# Q1_EAGLE_BRD.net
KiCad netlist of a schematic drawn in EAGLE
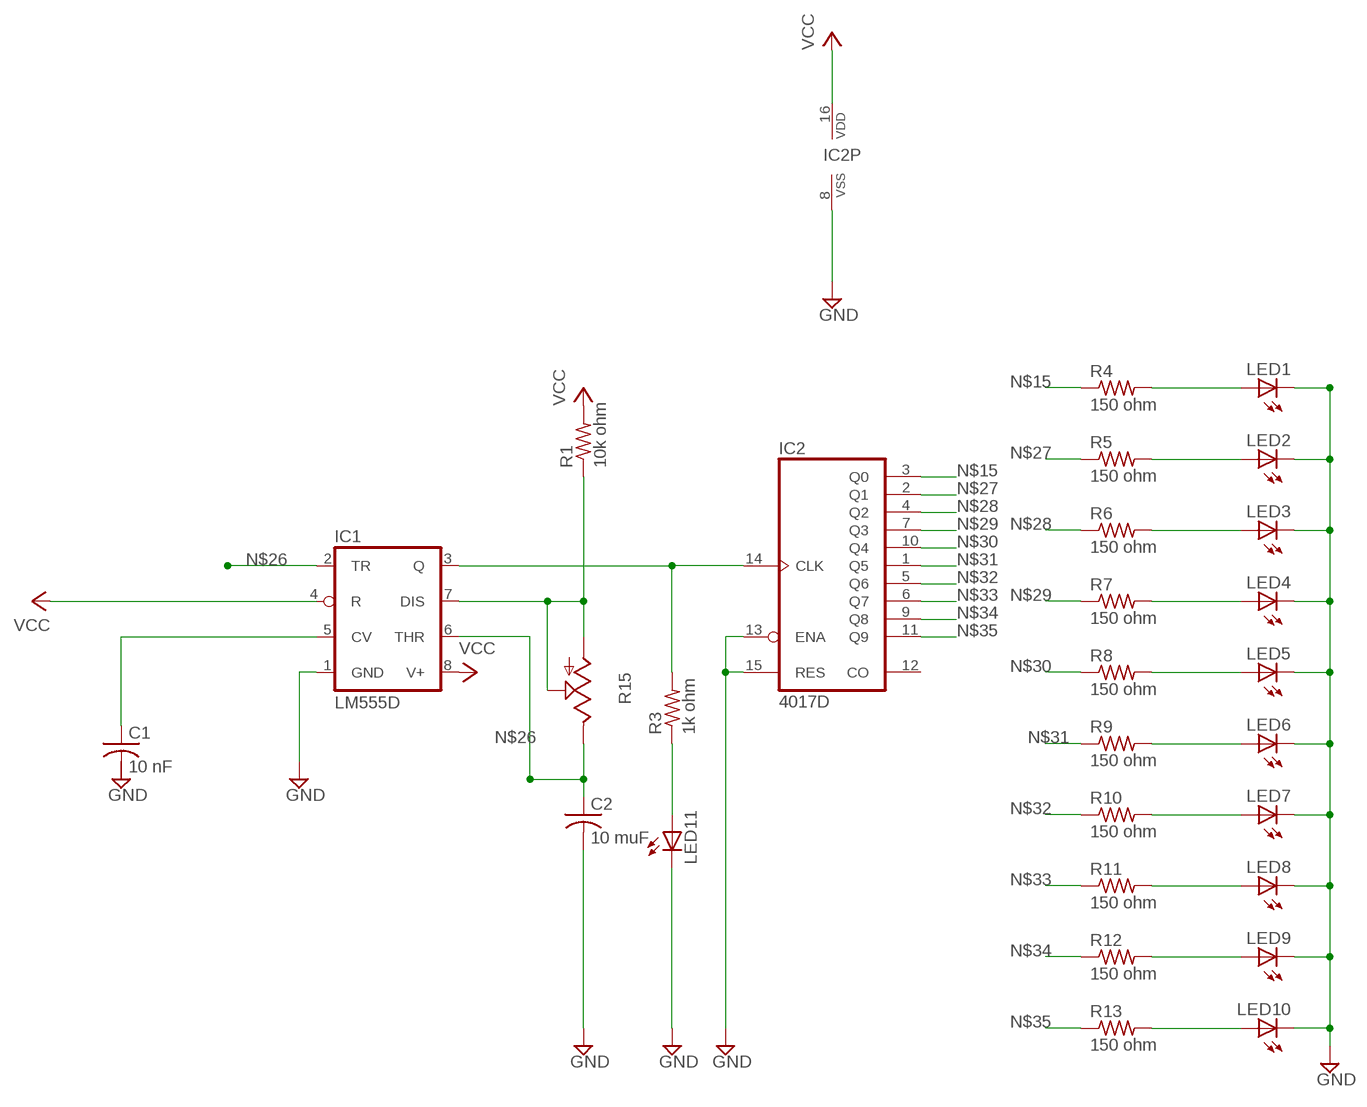
[diagram p0: schematic, sheet 1]

(export (version "E")
  (design (tool "Eeschema 10.0.6"))
  (components
    (comp (ref "C1")
      (value "10 nF")
      (footprint "eagle-import:C0805")
      (libsource (lib "eagle-import") (part "C-USC0805"))
    )
    (comp (ref "C2")
      (value "10 muF")
      (footprint "eagle-import:C0805")
      (libsource (lib "eagle-import") (part "C-USC0805"))
    )
    (comp (ref "IC1")
      (value "LM555D")
      (footprint "eagle-import:SO08")
      (libsource (lib "eagle-import") (part "555DLM"))
    )
    (comp (ref "IC2")
      (value "4017D")
      (footprint "eagle-import:SO16")
      (libsource (lib "eagle-import") (part "4017D"))
    )
    (comp (ref "LED1")
      (value "LED5MM")
      (footprint "eagle-import:LED5MM")
      (libsource (lib "eagle-import") (part "LED5MM"))
    )
    (comp (ref "LED2")
      (value "LED5MM")
      (footprint "eagle-import:LED5MM")
      (libsource (lib "eagle-import") (part "LED5MM"))
    )
    (comp (ref "LED3")
      (value "LED5MM")
      (footprint "eagle-import:LED5MM")
      (libsource (lib "eagle-import") (part "LED5MM"))
    )
    (comp (ref "LED4")
      (value "LED5MM")
      (footprint "eagle-import:LED5MM")
      (libsource (lib "eagle-import") (part "LED5MM"))
    )
    (comp (ref "LED5")
      (value "LED5MM")
      (footprint "eagle-import:LED5MM")
      (libsource (lib "eagle-import") (part "LED5MM"))
    )
    (comp (ref "LED6")
      (value "LED5MM")
      (footprint "eagle-import:LED5MM")
      (libsource (lib "eagle-import") (part "LED5MM"))
    )
    (comp (ref "LED7")
      (value "LED5MM")
      (footprint "eagle-import:LED5MM")
      (libsource (lib "eagle-import") (part "LED5MM"))
    )
    (comp (ref "LED8")
      (value "LED5MM")
      (footprint "eagle-import:LED5MM")
      (libsource (lib "eagle-import") (part "LED5MM"))
    )
    (comp (ref "LED9")
      (value "LED5MM")
      (footprint "eagle-import:LED5MM")
      (libsource (lib "eagle-import") (part "LED5MM"))
    )
    (comp (ref "LED10")
      (value "LED5MM")
      (footprint "eagle-import:LED5MM")
      (libsource (lib "eagle-import") (part "LED5MM"))
    )
    (comp (ref "LED11")
      (value "LED5MM")
      (footprint "eagle-import:LED5MM")
      (libsource (lib "eagle-import") (part "LED5MM"))
    )
    (comp (ref "R1")
      (value "10k ohm")
      (footprint "eagle-import:M1206")
      (libsource (lib "eagle-import") (part "R-US_M1206"))
    )
    (comp (ref "R3")
      (value "1k ohm")
      (footprint "eagle-import:M1206")
      (libsource (lib "eagle-import") (part "R-US_M1206"))
    )
    (comp (ref "R4")
      (value "150 ohm")
      (footprint "eagle-import:M1206")
      (libsource (lib "eagle-import") (part "R-US_M1206"))
    )
    (comp (ref "R5")
      (value "150 ohm")
      (footprint "eagle-import:M1206")
      (libsource (lib "eagle-import") (part "R-US_M1206"))
    )
    (comp (ref "R6")
      (value "150 ohm")
      (footprint "eagle-import:M1206")
      (libsource (lib "eagle-import") (part "R-US_M1206"))
    )
    (comp (ref "R7")
      (value "150 ohm")
      (footprint "eagle-import:M1206")
      (libsource (lib "eagle-import") (part "R-US_M1206"))
    )
    (comp (ref "R8")
      (value "150 ohm")
      (footprint "eagle-import:M1206")
      (libsource (lib "eagle-import") (part "R-US_M1206"))
    )
    (comp (ref "R9")
      (value "150 ohm")
      (footprint "eagle-import:M1206")
      (libsource (lib "eagle-import") (part "R-US_M1206"))
    )
    (comp (ref "R10")
      (value "150 ohm")
      (footprint "eagle-import:M1206")
      (libsource (lib "eagle-import") (part "R-US_M1206"))
    )
    (comp (ref "R11")
      (value "150 ohm")
      (footprint "eagle-import:M1206")
      (libsource (lib "eagle-import") (part "R-US_M1206"))
    )
    (comp (ref "R12")
      (value "150 ohm")
      (footprint "eagle-import:M1206")
      (libsource (lib "eagle-import") (part "R-US_M1206"))
    )
    (comp (ref "R13")
      (value "150 ohm")
      (footprint "eagle-import:M1206")
      (libsource (lib "eagle-import") (part "R-US_M1206"))
    )
    (comp (ref "R15")
      (value "TRIM_US-S63X")
      (footprint "eagle-import:S63X")
      (libsource (lib "eagle-import") (part "TRIM_US-S63X"))
    )
  )
  (nets
    (net (code "1") (name "/N$15") (class "Default")
      (node (ref "IC2") (pin "3") (pinfunction "Q0_3") (pintype "output"))
      (node (ref "R4") (pin "1") (pinfunction "1_1") (pintype "passive"))
    )
    (net (code "2") (name "/N$26") (class "Default")
      (node (ref "C2") (pin "1") (pinfunction "1_1") (pintype "passive"))
      (node (ref "IC1") (pin "2") (pinfunction "TR_2") (pintype "input"))
      (node (ref "IC1") (pin "6") (pinfunction "THR_6") (pintype "input"))
      (node (ref "R15") (pin "E") (pinfunction "E_E") (pintype "passive"))
    )
    (net (code "3") (name "/N$27") (class "Default")
      (node (ref "IC2") (pin "2") (pinfunction "Q1_2") (pintype "output"))
      (node (ref "R5") (pin "1") (pinfunction "1_1") (pintype "passive"))
    )
    (net (code "4") (name "/N$28") (class "Default")
      (node (ref "IC2") (pin "4") (pinfunction "Q2_4") (pintype "output"))
      (node (ref "R6") (pin "1") (pinfunction "1_1") (pintype "passive"))
    )
    (net (code "5") (name "/N$29") (class "Default")
      (node (ref "IC2") (pin "7") (pinfunction "Q3_7") (pintype "output"))
      (node (ref "R7") (pin "1") (pinfunction "1_1") (pintype "passive"))
    )
    (net (code "6") (name "/N$30") (class "Default")
      (node (ref "IC2") (pin "10") (pinfunction "Q4_10") (pintype "output"))
      (node (ref "R8") (pin "1") (pinfunction "1_1") (pintype "passive"))
    )
    (net (code "7") (name "/N$31") (class "Default")
      (node (ref "IC2") (pin "1") (pinfunction "Q5_1") (pintype "output"))
      (node (ref "R9") (pin "1") (pinfunction "1_1") (pintype "passive"))
    )
    (net (code "8") (name "/N$32") (class "Default")
      (node (ref "IC2") (pin "5") (pinfunction "Q6_5") (pintype "output"))
      (node (ref "R10") (pin "1") (pinfunction "1_1") (pintype "passive"))
    )
    (net (code "9") (name "/N$33") (class "Default")
      (node (ref "IC2") (pin "6") (pinfunction "Q7_6") (pintype "output"))
      (node (ref "R11") (pin "1") (pinfunction "1_1") (pintype "passive"))
    )
    (net (code "10") (name "/N$34") (class "Default")
      (node (ref "IC2") (pin "9") (pinfunction "Q8_9") (pintype "output"))
      (node (ref "R12") (pin "1") (pinfunction "1_1") (pintype "passive"))
    )
    (net (code "11") (name "/N$35") (class "Default")
      (node (ref "IC2") (pin "11") (pinfunction "Q9_11") (pintype "output"))
      (node (ref "R13") (pin "1") (pinfunction "1_1") (pintype "passive"))
    )
    (net (code "12") (name "GND") (class "Default")
      (node (ref "C2") (pin "2") (pinfunction "2_2") (pintype "passive"))
      (node (ref "IC1") (pin "1") (pinfunction "GND_1") (pintype "power_in"))
      (node (ref "IC2") (pin "13") (pinfunction "ENA_13") (pintype "input"))
      (node (ref "IC2") (pin "15") (pinfunction "RES_15") (pintype "input"))
      (node (ref "IC2") (pin "8") (pinfunction "VSS_8") (pintype "power_in"))
      (node (ref "LED1") (pin "K") (pinfunction "C_K") (pintype "passive"))
      (node (ref "LED10") (pin "K") (pinfunction "C_K") (pintype "passive"))
      (node (ref "LED11") (pin "K") (pinfunction "C_K") (pintype "passive"))
      (node (ref "LED2") (pin "K") (pinfunction "C_K") (pintype "passive"))
      (node (ref "LED3") (pin "K") (pinfunction "C_K") (pintype "passive"))
      (node (ref "LED4") (pin "K") (pinfunction "C_K") (pintype "passive"))
      (node (ref "LED5") (pin "K") (pinfunction "C_K") (pintype "passive"))
      (node (ref "LED6") (pin "K") (pinfunction "C_K") (pintype "passive"))
      (node (ref "LED7") (pin "K") (pinfunction "C_K") (pintype "passive"))
      (node (ref "LED8") (pin "K") (pinfunction "C_K") (pintype "passive"))
      (node (ref "LED9") (pin "K") (pinfunction "C_K") (pintype "passive"))
    )
    (net (code "13") (name "Net-(IC1-CV)") (class "Default")
      (node (ref "C1") (pin "1") (pinfunction "1_1") (pintype "passive"))
      (node (ref "IC1") (pin "5") (pinfunction "CV_5") (pintype "input"))
    )
    (net (code "14") (name "Net-(IC1-DIS)") (class "Default")
      (node (ref "IC1") (pin "7") (pinfunction "DIS_7") (pintype "input"))
      (node (ref "R1") (pin "1") (pinfunction "1_1") (pintype "passive"))
      (node (ref "R15") (pin "A") (pinfunction "A_A") (pintype "passive"))
      (node (ref "R15") (pin "S") (pinfunction "S_S") (pintype "passive"))
    )
    (net (code "15") (name "Net-(IC1-Q)") (class "Default")
      (node (ref "IC1") (pin "3") (pinfunction "Q_3") (pintype "output"))
      (node (ref "IC2") (pin "14") (pinfunction "CLK_14") (pintype "input"))
      (node (ref "R3") (pin "2") (pinfunction "2_2") (pintype "passive"))
    )
    (net (code "16") (name "Net-(LED1-PadA)") (class "Default")
      (node (ref "LED1") (pin "A") (pinfunction "A_A") (pintype "passive"))
      (node (ref "R4") (pin "2") (pinfunction "2_2") (pintype "passive"))
    )
    (net (code "17") (name "Net-(LED2-PadA)") (class "Default")
      (node (ref "LED2") (pin "A") (pinfunction "A_A") (pintype "passive"))
      (node (ref "R5") (pin "2") (pinfunction "2_2") (pintype "passive"))
    )
    (net (code "18") (name "Net-(LED3-PadA)") (class "Default")
      (node (ref "LED3") (pin "A") (pinfunction "A_A") (pintype "passive"))
      (node (ref "R6") (pin "2") (pinfunction "2_2") (pintype "passive"))
    )
    (net (code "19") (name "Net-(LED4-PadA)") (class "Default")
      (node (ref "LED4") (pin "A") (pinfunction "A_A") (pintype "passive"))
      (node (ref "R7") (pin "2") (pinfunction "2_2") (pintype "passive"))
    )
    (net (code "20") (name "Net-(LED5-PadA)") (class "Default")
      (node (ref "LED5") (pin "A") (pinfunction "A_A") (pintype "passive"))
      (node (ref "R8") (pin "2") (pinfunction "2_2") (pintype "passive"))
    )
    (net (code "21") (name "Net-(LED6-PadA)") (class "Default")
      (node (ref "LED6") (pin "A") (pinfunction "A_A") (pintype "passive"))
      (node (ref "R9") (pin "2") (pinfunction "2_2") (pintype "passive"))
    )
    (net (code "22") (name "Net-(LED7-PadA)") (class "Default")
      (node (ref "LED7") (pin "A") (pinfunction "A_A") (pintype "passive"))
      (node (ref "R10") (pin "2") (pinfunction "2_2") (pintype "passive"))
    )
    (net (code "23") (name "Net-(LED8-PadA)") (class "Default")
      (node (ref "LED8") (pin "A") (pinfunction "A_A") (pintype "passive"))
      (node (ref "R11") (pin "2") (pinfunction "2_2") (pintype "passive"))
    )
    (net (code "24") (name "Net-(LED9-PadA)") (class "Default")
      (node (ref "LED9") (pin "A") (pinfunction "A_A") (pintype "passive"))
      (node (ref "R12") (pin "2") (pinfunction "2_2") (pintype "passive"))
    )
    (net (code "25") (name "Net-(LED10-PadA)") (class "Default")
      (node (ref "LED10") (pin "A") (pinfunction "A_A") (pintype "passive"))
      (node (ref "R13") (pin "2") (pinfunction "2_2") (pintype "passive"))
    )
    (net (code "26") (name "Net-(LED11-PadA)") (class "Default")
      (node (ref "LED11") (pin "A") (pinfunction "A_A") (pintype "passive"))
      (node (ref "R3") (pin "1") (pinfunction "1_1") (pintype "passive"))
    )
    (net (code "27") (name "VCC") (class "Default")
      (node (ref "IC1") (pin "4") (pinfunction "R_4") (pintype "input"))
      (node (ref "IC1") (pin "8") (pinfunction "V+_8") (pintype "power_in"))
      (node (ref "IC2") (pin "16") (pinfunction "VDD_16") (pintype "power_in"))
      (node (ref "R1") (pin "2") (pinfunction "2_2") (pintype "passive"))
    )
    (net (code "28") (name "unconnected-(C1-Pad2)") (class "Default")
      (node (ref "C1") (pin "2") (pinfunction "2_2") (pintype "passive"))
    )
    (net (code "29") (name "unconnected-(IC2A-CO-Pad12)") (class "Default")
      (node (ref "IC2") (pin "12") (pinfunction "CO_12") (pintype "output"))
    )
  )
)
